# Rocky_Switch_Relay.net
KiCad netlist of a schematic drawn in EAGLE
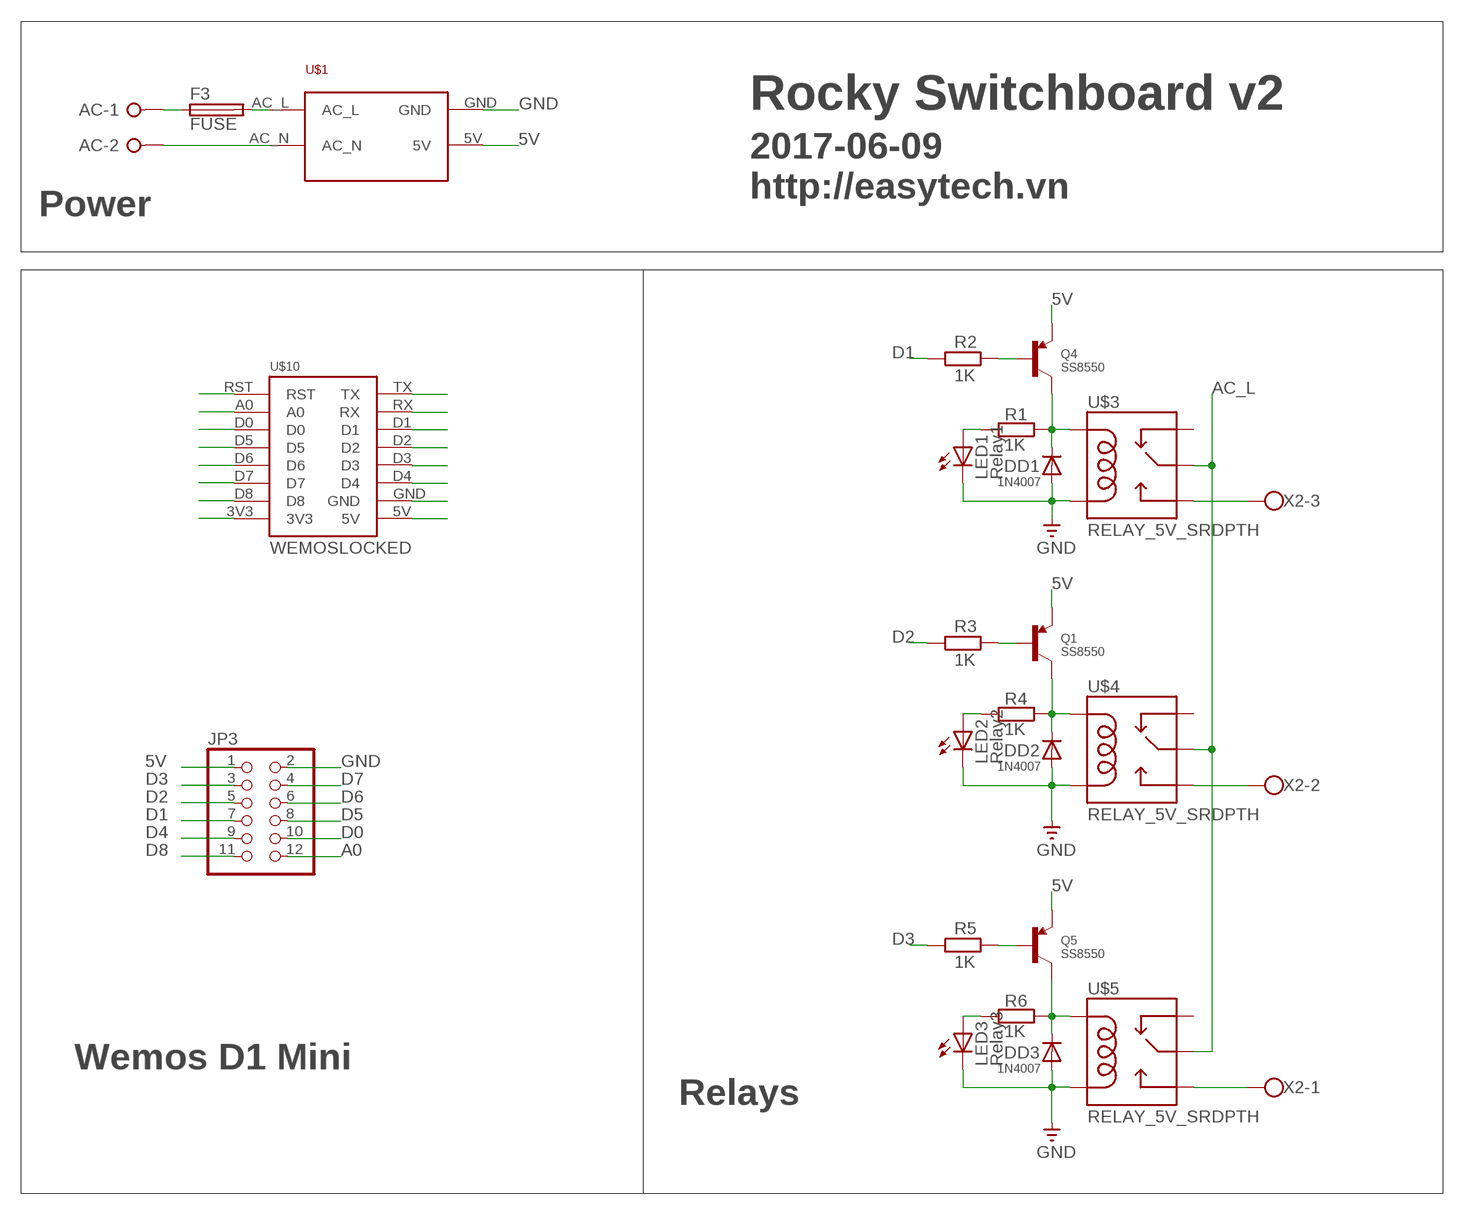
[diagram p0: schematic, sheet 1]

(export (version "E")
  (design (tool "Eeschema 10.0.6"))
  (components
    (comp (ref "AC")
      (value "W237-02P")
      (footprint "eagle-import:W237-132")
      (libsource (lib "eagle-import") (part "W237-02P"))
    )
    (comp (ref "DD1")
      (value "1N4007")
      (footprint "eagle-import:SMADIODE")
      (libsource (lib "eagle-import") (part "DIODESMA"))
    )
    (comp (ref "DD2")
      (value "1N4007")
      (footprint "eagle-import:SMADIODE")
      (libsource (lib "eagle-import") (part "DIODESMA"))
    )
    (comp (ref "DD3")
      (value "1N4007")
      (footprint "eagle-import:SMADIODE")
      (libsource (lib "eagle-import") (part "DIODESMA"))
    )
    (comp (ref "F3")
      (value "FUSE")
      (footprint "eagle-import:TE5")
      (libsource (lib "eagle-import") (part "FUSETE5"))
    )
    (comp (ref "JP3")
      (value "PINHD-2X6")
      (footprint "eagle-import:2X06")
      (libsource (lib "eagle-import") (part "PINHD-2X6"))
    )
    (comp (ref "LED1")
      (value "Relay1")
      (footprint "eagle-import:CHIP-LED0805")
      (libsource (lib "eagle-import") (part "LEDCHIP-LED0805"))
    )
    (comp (ref "LED2")
      (value "Relay2")
      (footprint "eagle-import:CHIP-LED0805")
      (libsource (lib "eagle-import") (part "LEDCHIP-LED0805"))
    )
    (comp (ref "LED3")
      (value "Relay3")
      (footprint "eagle-import:CHIP-LED0805")
      (libsource (lib "eagle-import") (part "LEDCHIP-LED0805"))
    )
    (comp (ref "Q1")
      (value "SS8550")
      (footprint "eagle-import:SOT23-W")
      (libsource (lib "eagle-import") (part "TRANSISTOR_PNPSOT23-WAVE"))
    )
    (comp (ref "Q4")
      (value "SS8550")
      (footprint "eagle-import:SOT23-W")
      (libsource (lib "eagle-import") (part "TRANSISTOR_PNPSOT23-WAVE"))
    )
    (comp (ref "Q5")
      (value "SS8550")
      (footprint "eagle-import:SOT23-W")
      (libsource (lib "eagle-import") (part "TRANSISTOR_PNPSOT23-WAVE"))
    )
    (comp (ref "R1")
      (value "1K")
      (footprint "eagle-import:R0805")
      (libsource (lib "eagle-import") (part "R-EU_R0805"))
    )
    (comp (ref "R2")
      (value "1K")
      (footprint "eagle-import:R0805")
      (libsource (lib "eagle-import") (part "R-EU_R0805"))
    )
    (comp (ref "R3")
      (value "1K")
      (footprint "eagle-import:R0805")
      (libsource (lib "eagle-import") (part "R-EU_R0805"))
    )
    (comp (ref "R4")
      (value "1K")
      (footprint "eagle-import:R0805")
      (libsource (lib "eagle-import") (part "R-EU_R0805"))
    )
    (comp (ref "R5")
      (value "1K")
      (footprint "eagle-import:R0805")
      (libsource (lib "eagle-import") (part "R-EU_R0805"))
    )
    (comp (ref "R6")
      (value "1K")
      (footprint "eagle-import:R0805")
      (libsource (lib "eagle-import") (part "R-EU_R0805"))
    )
    (comp (ref "U$1")
      (value "POWER_SUPPLY_220VAC_5V")
      (footprint "eagle-import:POWER_SUPPLY_220VAC_5V")
      (libsource (lib "eagle-import") (part "POWER_SUPPLY_220VAC_5V"))
    )
    (comp (ref "U$3")
      (value "RELAY_5V_SRDPTH")
      (footprint "eagle-import:SRD-05VDC-SL-C")
      (libsource (lib "eagle-import") (part "RELAY_5V_SRDPTH"))
    )
    (comp (ref "U$4")
      (value "RELAY_5V_SRDPTH")
      (footprint "eagle-import:SRD-05VDC-SL-C")
      (libsource (lib "eagle-import") (part "RELAY_5V_SRDPTH"))
    )
    (comp (ref "U$5")
      (value "RELAY_5V_SRDPTH")
      (footprint "eagle-import:SRD-05VDC-SL-C")
      (libsource (lib "eagle-import") (part "RELAY_5V_SRDPTH"))
    )
    (comp (ref "U$10")
      (value "WEMOSLOCKED")
      (footprint "eagle-import:WEMOS_LOCKED")
      (libsource (lib "eagle-import") (part "WEMOSLOCKED"))
    )
    (comp (ref "X2")
      (value "W237-103")
      (footprint "eagle-import:W237-103")
      (fields (field (name "MPN") "237-103"))
      (libsource (lib "eagle-import") (part "W237-103"))
    )
  )
  (nets
    (net (code "1") (name "/5V") (class "Default")
      (node (ref "JP3") (pin "1") (pinfunction "1_1") (pintype "passive"))
      (node (ref "Q1") (pin "2") (pinfunction "E_2") (pintype "passive"))
      (node (ref "Q4") (pin "2") (pinfunction "E_2") (pintype "passive"))
      (node (ref "Q5") (pin "2") (pinfunction "E_2") (pintype "passive"))
      (node (ref "U$1") (pin "5V") (pinfunction "5V_5V") (pintype "bidirectional"))
      (node (ref "U$10") (pin "5V") (pinfunction "5V_5V") (pintype "bidirectional"))
    )
    (net (code "2") (name "/A0") (class "Default")
      (node (ref "JP3") (pin "12") (pinfunction "12_12") (pintype "passive"))
      (node (ref "U$10") (pin "A0") (pinfunction "A0_A0") (pintype "bidirectional"))
    )
    (net (code "3") (name "/AC_L") (class "Default")
      (node (ref "F3") (pin "2") (pinfunction "2_2") (pintype "passive"))
      (node (ref "U$1") (pin "AC_L") (pinfunction "AC_L_AC_L") (pintype "bidirectional"))
      (node (ref "U$3") (pin "SWCOMMON") (pinfunction "SWCOMMON_SWCOMMON") (pintype "bidirectional"))
      (node (ref "U$4") (pin "SWCOMMON") (pinfunction "SWCOMMON_SWCOMMON") (pintype "bidirectional"))
      (node (ref "U$5") (pin "SWCOMMON") (pinfunction "SWCOMMON_SWCOMMON") (pintype "bidirectional"))
    )
    (net (code "4") (name "/D0") (class "Default")
      (node (ref "JP3") (pin "10") (pinfunction "10_10") (pintype "passive"))
      (node (ref "U$10") (pin "D0") (pinfunction "D0_D0") (pintype "bidirectional"))
    )
    (net (code "5") (name "/D1") (class "Default")
      (node (ref "JP3") (pin "7") (pinfunction "7_7") (pintype "passive"))
      (node (ref "R2") (pin "1") (pinfunction "1_1") (pintype "passive"))
      (node (ref "U$10") (pin "D1") (pinfunction "D1_D1") (pintype "bidirectional"))
    )
    (net (code "6") (name "/D2") (class "Default")
      (node (ref "JP3") (pin "5") (pinfunction "5_5") (pintype "passive"))
      (node (ref "R3") (pin "1") (pinfunction "1_1") (pintype "passive"))
      (node (ref "U$10") (pin "D2") (pinfunction "D2_D2") (pintype "bidirectional"))
    )
    (net (code "7") (name "/D3") (class "Default")
      (node (ref "JP3") (pin "3") (pinfunction "3_3") (pintype "passive"))
      (node (ref "R5") (pin "1") (pinfunction "1_1") (pintype "passive"))
      (node (ref "U$10") (pin "D3") (pinfunction "D3_D3") (pintype "bidirectional"))
    )
    (net (code "8") (name "/D4") (class "Default")
      (node (ref "JP3") (pin "9") (pinfunction "9_9") (pintype "passive"))
      (node (ref "U$10") (pin "D4") (pinfunction "D4_D4") (pintype "bidirectional"))
    )
    (net (code "9") (name "/D5") (class "Default")
      (node (ref "JP3") (pin "8") (pinfunction "8_8") (pintype "passive"))
      (node (ref "U$10") (pin "D5") (pinfunction "D5_D5") (pintype "bidirectional"))
    )
    (net (code "10") (name "/D6") (class "Default")
      (node (ref "JP3") (pin "6") (pinfunction "6_6") (pintype "passive"))
      (node (ref "U$10") (pin "D6") (pinfunction "D6_D6") (pintype "bidirectional"))
    )
    (net (code "11") (name "/D7") (class "Default")
      (node (ref "JP3") (pin "4") (pinfunction "4_4") (pintype "passive"))
      (node (ref "U$10") (pin "D7") (pinfunction "D7_D7") (pintype "bidirectional"))
    )
    (net (code "12") (name "/D8") (class "Default")
      (node (ref "JP3") (pin "11") (pinfunction "11_11") (pintype "passive"))
      (node (ref "U$10") (pin "D8") (pinfunction "D8_D8") (pintype "bidirectional"))
    )
    (net (code "13") (name "GND") (class "Default")
      (node (ref "DD1") (pin "A") (pinfunction "A_A") (pintype "passive"))
      (node (ref "DD2") (pin "A") (pinfunction "A_A") (pintype "passive"))
      (node (ref "DD3") (pin "A") (pinfunction "A_A") (pintype "passive"))
      (node (ref "JP3") (pin "2") (pinfunction "2_2") (pintype "passive"))
      (node (ref "LED1") (pin "C") (pinfunction "C_C") (pintype "passive"))
      (node (ref "LED2") (pin "C") (pinfunction "C_C") (pintype "passive"))
      (node (ref "LED3") (pin "C") (pinfunction "C_C") (pintype "passive"))
      (node (ref "U$1") (pin "GND") (pinfunction "GND_GND") (pintype "bidirectional"))
      (node (ref "U$10") (pin "GND") (pinfunction "GND_GND") (pintype "bidirectional"))
      (node (ref "U$3") (pin "COIL0") (pinfunction "COIL0_COIL0") (pintype "bidirectional"))
      (node (ref "U$4") (pin "COIL0") (pinfunction "COIL0_COIL0") (pintype "bidirectional"))
      (node (ref "U$5") (pin "COIL0") (pinfunction "COIL0_COIL0") (pintype "bidirectional"))
    )
    (net (code "14") (name "Net-(ACA-KL)") (class "Default")
      (node (ref "AC") (pin "1") (pinfunction "KL_1") (pintype "passive"))
      (node (ref "F3") (pin "1") (pinfunction "1_1") (pintype "passive"))
    )
    (net (code "15") (name "Net-(ACB-KL)") (class "Default")
      (node (ref "AC") (pin "2") (pinfunction "KL_2") (pintype "passive"))
      (node (ref "U$1") (pin "AC_N") (pinfunction "AC_N_AC_N") (pintype "bidirectional"))
    )
    (net (code "16") (name "Net-(LED1-PadA)") (class "Default")
      (node (ref "LED1") (pin "A") (pinfunction "A_A") (pintype "passive"))
      (node (ref "R1") (pin "2") (pinfunction "2_2") (pintype "passive"))
    )
    (net (code "17") (name "Net-(LED2-PadA)") (class "Default")
      (node (ref "LED2") (pin "A") (pinfunction "A_A") (pintype "passive"))
      (node (ref "R4") (pin "2") (pinfunction "2_2") (pintype "passive"))
    )
    (net (code "18") (name "Net-(LED3-PadA)") (class "Default")
      (node (ref "LED3") (pin "A") (pinfunction "A_A") (pintype "passive"))
      (node (ref "R6") (pin "2") (pinfunction "2_2") (pintype "passive"))
    )
    (net (code "19") (name "Net-(Q1-B)") (class "Default")
      (node (ref "Q1") (pin "1") (pinfunction "B_1") (pintype "passive"))
      (node (ref "R3") (pin "2") (pinfunction "2_2") (pintype "passive"))
    )
    (net (code "20") (name "Net-(Q1-C)") (class "Default")
      (node (ref "DD2") (pin "C") (pinfunction "C_C") (pintype "passive"))
      (node (ref "Q1") (pin "3") (pinfunction "C_3") (pintype "passive"))
      (node (ref "R4") (pin "1") (pinfunction "1_1") (pintype "passive"))
      (node (ref "U$4") (pin "COIL1") (pinfunction "COIL1_COIL1") (pintype "bidirectional"))
    )
    (net (code "21") (name "Net-(Q4-B)") (class "Default")
      (node (ref "Q4") (pin "1") (pinfunction "B_1") (pintype "passive"))
      (node (ref "R2") (pin "2") (pinfunction "2_2") (pintype "passive"))
    )
    (net (code "22") (name "Net-(Q4-C)") (class "Default")
      (node (ref "DD1") (pin "C") (pinfunction "C_C") (pintype "passive"))
      (node (ref "Q4") (pin "3") (pinfunction "C_3") (pintype "passive"))
      (node (ref "R1") (pin "1") (pinfunction "1_1") (pintype "passive"))
      (node (ref "U$3") (pin "COIL1") (pinfunction "COIL1_COIL1") (pintype "bidirectional"))
    )
    (net (code "23") (name "Net-(Q5-B)") (class "Default")
      (node (ref "Q5") (pin "1") (pinfunction "B_1") (pintype "passive"))
      (node (ref "R5") (pin "2") (pinfunction "2_2") (pintype "passive"))
    )
    (net (code "24") (name "Net-(Q5-C)") (class "Default")
      (node (ref "DD3") (pin "C") (pinfunction "C_C") (pintype "passive"))
      (node (ref "Q5") (pin "3") (pinfunction "C_3") (pintype "passive"))
      (node (ref "R6") (pin "1") (pinfunction "1_1") (pintype "passive"))
      (node (ref "U$5") (pin "COIL1") (pinfunction "COIL1_COIL1") (pintype "bidirectional"))
    )
    (net (code "25") (name "Net-(X2A-KL)") (class "Default")
      (node (ref "U$5") (pin "SWOPEN") (pinfunction "SWOPEN_SWOPEN") (pintype "bidirectional"))
      (node (ref "X2") (pin "1") (pinfunction "KL_1") (pintype "passive"))
    )
    (net (code "26") (name "Net-(X2B-KL)") (class "Default")
      (node (ref "U$4") (pin "SWOPEN") (pinfunction "SWOPEN_SWOPEN") (pintype "bidirectional"))
      (node (ref "X2") (pin "2") (pinfunction "KL_2") (pintype "passive"))
    )
    (net (code "27") (name "Net-(X2C-KL)") (class "Default")
      (node (ref "U$3") (pin "SWOPEN") (pinfunction "SWOPEN_SWOPEN") (pintype "bidirectional"))
      (node (ref "X2") (pin "3") (pinfunction "KL_3") (pintype "passive"))
    )
    (net (code "28") (name "unconnected-(U$3-SWCLOSE-PadSWCLOSED)") (class "Default")
      (node (ref "U$3") (pin "SWCLOSED") (pinfunction "SWCLOSE_SWCLOSED") (pintype "bidirectional"))
    )
    (net (code "29") (name "unconnected-(U$4-SWCLOSE-PadSWCLOSED)") (class "Default")
      (node (ref "U$4") (pin "SWCLOSED") (pinfunction "SWCLOSE_SWCLOSED") (pintype "bidirectional"))
    )
    (net (code "30") (name "unconnected-(U$5-SWCLOSE-PadSWCLOSED)") (class "Default")
      (node (ref "U$5") (pin "SWCLOSED") (pinfunction "SWCLOSE_SWCLOSED") (pintype "bidirectional"))
    )
    (net (code "31") (name "unconnected-(U$10-Pad3V3)") (class "Default")
      (node (ref "U$10") (pin "3V3") (pinfunction "3V3_3V3") (pintype "bidirectional"))
    )
    (net (code "32") (name "unconnected-(U$10-PadRST)") (class "Default")
      (node (ref "U$10") (pin "RST") (pinfunction "RST_RST") (pintype "bidirectional"))
    )
    (net (code "33") (name "unconnected-(U$10-PadRX)") (class "Default")
      (node (ref "U$10") (pin "RX") (pinfunction "RX_RX") (pintype "bidirectional"))
    )
    (net (code "34") (name "unconnected-(U$10-PadTX)") (class "Default")
      (node (ref "U$10") (pin "TX") (pinfunction "TX_TX") (pintype "bidirectional"))
    )
  )
)
